# Grove_expansion_v4_for_box.net
KiCad netlist of a schematic drawn in EAGLE
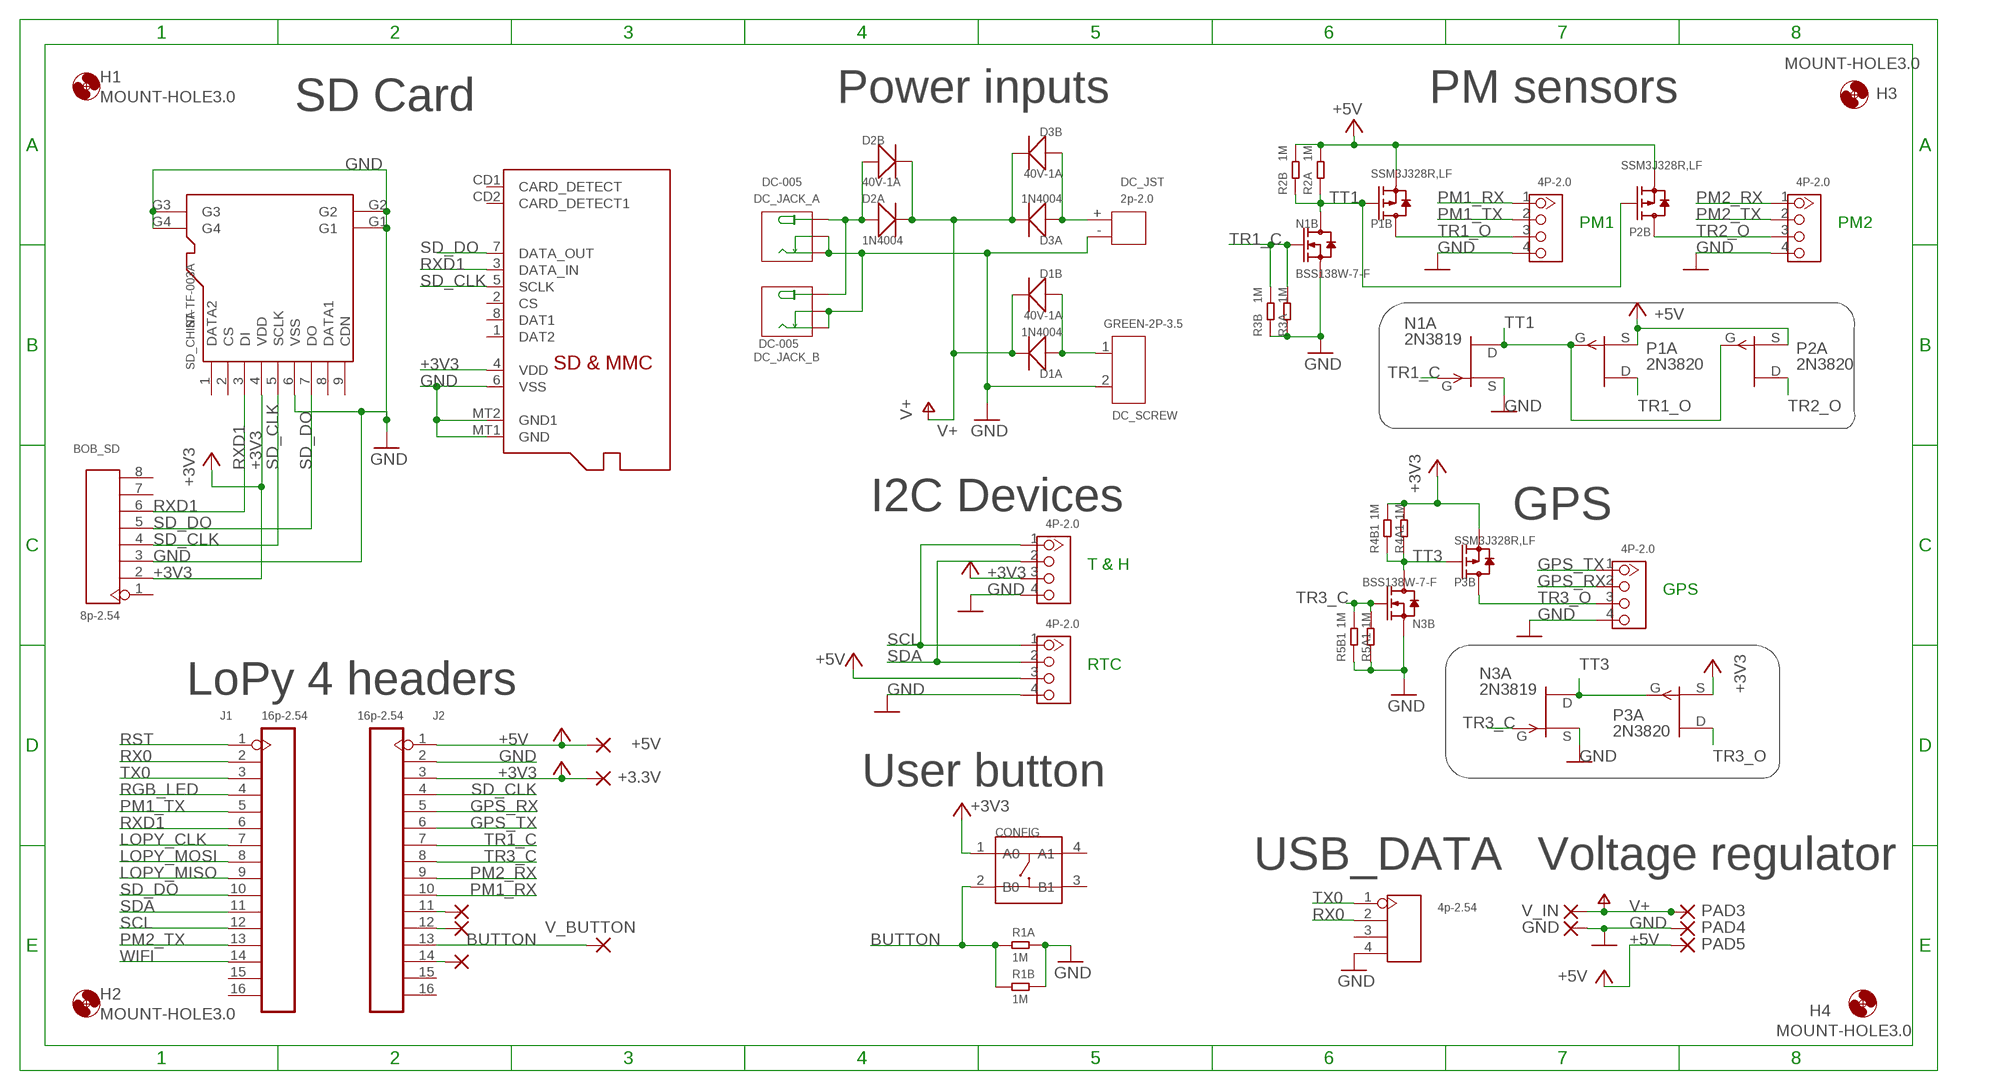
[diagram p0: schematic, sheet 1]

(export (version "E")
  (design (tool "Eeschema 10.0.6"))
  (components
    (comp (ref "+3.3V")
      (value "2,15/1,0")
      (footprint "eagle-import:2,15_1,0")
      (libsource (lib "eagle-import") (part "2,15/1,0"))
    )
    (comp (ref "+5V")
      (value "2,15/1,0")
      (footprint "eagle-import:2,15_1,0")
      (libsource (lib "eagle-import") (part "2,15/1,0"))
    )
    (comp (ref "BOB_SD")
      (value "8p-2.54")
      (footprint "eagle-import:H8-2.54")
      (fields (field (name "MPN") "F185-1108A1BSYC1"))
      (libsource (lib "eagle-import") (part "DIP-BLACK-FEMALE-HEADER-VERT(8P-2.54)"))
    )
    (comp (ref "CONFIG")
      (value "DIP-SWITCH-TACTILE-SPST-NO/TS-1109(4P-D6.0MM)'TS-1109'")
      (footprint "eagle-import:SW4-6.0X6.0X5.0MM")
      (libsource (lib "eagle-import") (part "DIP-SWITCH-TACTILE-SPST-NO/TS-1109(4P-D6.0MM)'TS-1109'"))
    )
    (comp (ref "D1A")
      (value "1N4004")
      (footprint "eagle-import:DO-41")
      (libsource (lib "eagle-import") (part "DIP-DIODE-400V-1A(DO-41)"))
    )
    (comp (ref "D1B")
      (value "40V-1A")
      (footprint "eagle-import:DO-214AC")
      (fields (field (name "MPN") "1N5819"))
      (libsource (lib "eagle-import") (part "SMD-DIODE-SCHOTTKY-40V-1A(DO-214AC)"))
    )
    (comp (ref "D2A")
      (value "1N4004")
      (footprint "eagle-import:DO-41")
      (libsource (lib "eagle-import") (part "DIP-DIODE-400V-1A(DO-41)"))
    )
    (comp (ref "D2B")
      (value "40V-1A")
      (footprint "eagle-import:DO-214AC")
      (fields (field (name "MPN") "1N5819"))
      (libsource (lib "eagle-import") (part "SMD-DIODE-SCHOTTKY-40V-1A(DO-214AC)"))
    )
    (comp (ref "D3A")
      (value "1N4004")
      (footprint "eagle-import:DO-41")
      (libsource (lib "eagle-import") (part "DIP-DIODE-400V-1A(DO-41)"))
    )
    (comp (ref "D3B")
      (value "40V-1A")
      (footprint "eagle-import:DO-214AC")
      (fields (field (name "MPN") "1N5819"))
      (libsource (lib "eagle-import") (part "SMD-DIODE-SCHOTTKY-40V-1A(DO-214AC)"))
    )
    (comp (ref "DC_JACK_A")
      (value "DC-005")
      (footprint "eagle-import:DCJ3P-14.2X11.0X9.0MM")
      (libsource (lib "eagle-import") (part "CONN-POWER-JACK-2.1MM(DC-005)"))
    )
    (comp (ref "DC_JACK_B")
      (value "DC-005")
      (footprint "eagle-import:DCJ3P-14.2X11.0X9.0MM")
      (libsource (lib "eagle-import") (part "CONN-POWER-JACK-2.1MM(DC-005)"))
    )
    (comp (ref "DC_JST")
      (value "2p-2.0")
      (footprint "eagle-import:H2-2.0-6X4.5MM")
      (libsource (lib "eagle-import") (part "DIP-JST-2P-2.0"))
    )
    (comp (ref "DC_SCREW")
      (value "GREEN-2P-3.5")
      (footprint "eagle-import:H2-3.5-7.0X7.0MM")
      (libsource (lib "eagle-import") (part "SCREW-TERMINAL-GREEN(2P-3.5)"))
    )
    (comp (ref "GND")
      (value "2,15/1,0")
      (footprint "eagle-import:2,15_1,0")
      (libsource (lib "eagle-import") (part "2,15/1,0"))
    )
    (comp (ref "GPS-(DIG)")
      (value "4P-2.0")
      (footprint "eagle-import:HW4-2.0")
      (libsource (lib "eagle-import") (part "GROVE-CONNECTOR-DIP(4P-2.0)"))
    )
    (comp (ref "H1")
      (value "MOUNT-HOLE3.0")
      (footprint "eagle-import:3,0")
      (libsource (lib "eagle-import") (part "MOUNT-HOLE3.0"))
    )
    (comp (ref "H2")
      (value "MOUNT-HOLE3.0")
      (footprint "eagle-import:3,0")
      (libsource (lib "eagle-import") (part "MOUNT-HOLE3.0"))
    )
    (comp (ref "H3")
      (value "MOUNT-HOLE3.0")
      (footprint "eagle-import:3,0")
      (libsource (lib "eagle-import") (part "MOUNT-HOLE3.0"))
    )
    (comp (ref "H4")
      (value "MOUNT-HOLE3.0")
      (footprint "eagle-import:3,0")
      (libsource (lib "eagle-import") (part "MOUNT-HOLE3.0"))
    )
    (comp (ref "J1")
      (value "16p-2.54")
      (footprint "eagle-import:H16-2.54")
      (fields (field (name "MPN") "P125-1116A0BS116AX"))
      (libsource (lib "eagle-import") (part "DIP-BLACK-MALE-HEADER-VERT(16P-2.54)"))
    )
    (comp (ref "J2")
      (value "16p-2.54")
      (footprint "eagle-import:H16-2.54")
      (fields (field (name "MPN") "P125-1116A0BS116AX"))
      (libsource (lib "eagle-import") (part "DIP-BLACK-MALE-HEADER-VERT(16P-2.54)"))
    )
    (comp (ref "N1A")
      (value "2N3819")
      (footprint "eagle-import:TO92")
      (libsource (lib "eagle-import") (part "2N3819"))
    )
    (comp (ref "N1B")
      (value "BSS138W-7-F")
      (footprint "eagle-import:SOT-23")
      (libsource (lib "eagle-import") (part "SMD-MOSFET-N-CH-50V-200MA-BSS138W-7-F(SOT-23)"))
    )
    (comp (ref "N3A")
      (value "2N3819")
      (footprint "eagle-import:TO92")
      (libsource (lib "eagle-import") (part "2N3819"))
    )
    (comp (ref "N3B")
      (value "BSS138W-7-F")
      (footprint "eagle-import:SOT-23")
      (libsource (lib "eagle-import") (part "SMD-MOSFET-N-CH-50V-200MA-BSS138W-7-F(SOT-23)"))
    )
    (comp (ref "P1A")
      (value "2N3820")
      (footprint "eagle-import:TO92")
      (libsource (lib "eagle-import") (part "2N3820"))
    )
    (comp (ref "P1B")
      (value "SSM3J328R,LF")
      (footprint "eagle-import:SOT-23")
      (libsource (lib "eagle-import") (part "SMD-MOSFET-P-CH-20V-6A-SSM3J328R(SOT-23)"))
    )
    (comp (ref "P2A")
      (value "2N3820")
      (footprint "eagle-import:TO92")
      (libsource (lib "eagle-import") (part "2N3820"))
    )
    (comp (ref "P2B")
      (value "SSM3J328R,LF")
      (footprint "eagle-import:SOT-23")
      (libsource (lib "eagle-import") (part "SMD-MOSFET-P-CH-20V-6A-SSM3J328R(SOT-23)"))
    )
    (comp (ref "P3A")
      (value "2N3820")
      (footprint "eagle-import:TO92")
      (libsource (lib "eagle-import") (part "2N3820"))
    )
    (comp (ref "P3B")
      (value "SSM3J328R,LF")
      (footprint "eagle-import:SOT-23")
      (libsource (lib "eagle-import") (part "SMD-MOSFET-P-CH-20V-6A-SSM3J328R(SOT-23)"))
    )
    (comp (ref "P13")
      (value "2,15/1,0")
      (footprint "eagle-import:2,15_1,0")
      (libsource (lib "eagle-import") (part "2,15/1,0"))
    )
    (comp (ref "P15")
      (value "2,15/1,0")
      (footprint "eagle-import:2,15_1,0")
      (libsource (lib "eagle-import") (part "2,15/1,0"))
    )
    (comp (ref "P16")
      (value "2,15/1,0")
      (footprint "eagle-import:2,15_1,0")
      (libsource (lib "eagle-import") (part "2,15/1,0"))
    )
    (comp (ref "PAD3")
      (value "1,6/0,8")
      (footprint "eagle-import:1,6_0,8")
      (libsource (lib "eagle-import") (part "1,6/0,8"))
    )
    (comp (ref "PAD4")
      (value "1,6/0,8")
      (footprint "eagle-import:1,6_0,8")
      (libsource (lib "eagle-import") (part "1,6/0,8"))
    )
    (comp (ref "PAD5")
      (value "1,6/0,8")
      (footprint "eagle-import:1,6_0,8")
      (libsource (lib "eagle-import") (part "1,6/0,8"))
    )
    (comp (ref "PM1-(UART)")
      (value "4P-2.0")
      (footprint "eagle-import:HW4-2.0")
      (libsource (lib "eagle-import") (part "GROVE-CONNECTOR-DIP(4P-2.0)"))
    )
    (comp (ref "PM2-(UART)")
      (value "4P-2.0")
      (footprint "eagle-import:HW4-2.0")
      (libsource (lib "eagle-import") (part "GROVE-CONNECTOR-DIP(4P-2.0)"))
    )
    (comp (ref "R1A")
      (value "1M")
      (footprint "eagle-import:PR-D2.3XL6.5MM")
      (fields (field (name "MPN") "FHCFR-1/4W-105J"))
      (libsource (lib "eagle-import") (part "DIP-RES-1M-5%-1/4W(PR-D2.3XL6.5MM)"))
    )
    (comp (ref "R1B")
      (value "1M")
      (footprint "eagle-import:R0603")
      (fields (field (name "MPN") "RC0603FR-071ML"))
      (libsource (lib "eagle-import") (part "SMD-RES-1M-1%-1/10W(0603)"))
    )
    (comp (ref "R2A")
      (value "1M")
      (footprint "eagle-import:PR-D2.3XL6.5MM")
      (fields (field (name "MPN") "FHCFR-1/4W-105J"))
      (libsource (lib "eagle-import") (part "DIP-RES-1M-5%-1/4W(PR-D2.3XL6.5MM)"))
    )
    (comp (ref "R2B")
      (value "1M")
      (footprint "eagle-import:R0603")
      (fields (field (name "MPN") "RC0603FR-071ML"))
      (libsource (lib "eagle-import") (part "SMD-RES-1M-1%-1/10W(0603)"))
    )
    (comp (ref "R3A")
      (value "1M")
      (footprint "eagle-import:PR-D2.3XL6.5MM")
      (fields (field (name "MPN") "FHCFR-1/4W-105J"))
      (libsource (lib "eagle-import") (part "DIP-RES-1M-5%-1/4W(PR-D2.3XL6.5MM)"))
    )
    (comp (ref "R3B")
      (value "1M")
      (footprint "eagle-import:R0603")
      (fields (field (name "MPN") "RC0603FR-071ML"))
      (libsource (lib "eagle-import") (part "SMD-RES-1M-1%-1/10W(0603)"))
    )
    (comp (ref "R4A1")
      (value "1M")
      (footprint "eagle-import:PR-D2.3XL6.5MM")
      (fields (field (name "MPN") "FHCFR-1/4W-105J"))
      (libsource (lib "eagle-import") (part "DIP-RES-1M-5%-1/4W(PR-D2.3XL6.5MM)"))
    )
    (comp (ref "R4B1")
      (value "1M")
      (footprint "eagle-import:R0603")
      (fields (field (name "MPN") "RC0603FR-071ML"))
      (libsource (lib "eagle-import") (part "SMD-RES-1M-1%-1/10W(0603)"))
    )
    (comp (ref "R5A1")
      (value "1M")
      (footprint "eagle-import:PR-D2.3XL6.5MM")
      (fields (field (name "MPN") "FHCFR-1/4W-105J"))
      (libsource (lib "eagle-import") (part "DIP-RES-1M-5%-1/4W(PR-D2.3XL6.5MM)"))
    )
    (comp (ref "R5B1")
      (value "1M")
      (footprint "eagle-import:R0603")
      (fields (field (name "MPN") "RC0603FR-071ML"))
      (libsource (lib "eagle-import") (part "SMD-RES-1M-1%-1/10W(0603)"))
    )
    (comp (ref "RTC-(I2C)")
      (value "4P-2.0")
      (footprint "eagle-import:HW4-2.0")
      (libsource (lib "eagle-import") (part "GROVE-CONNECTOR-DIP(4P-2.0)"))
    )
    (comp (ref "SD_CHINA")
      (value "ST-TF-003A")
      (footprint "eagle-import:MICRO-SD9+4P-SMD-16.1X14.5X1.85MM")
      (libsource (lib "eagle-import") (part "MICRO-SD-CARD-SOCKET-9P(ST-TF-003A)"))
    )
    (comp (ref "SD_UK")
      (value "MICROSD")
      (footprint "eagle-import:MICROSD")
      (libsource (lib "eagle-import") (part "MICROSD"))
    )
    (comp (ref "TH-(I2C)")
      (value "4P-2.0")
      (footprint "eagle-import:HW4-2.0")
      (libsource (lib "eagle-import") (part "GROVE-CONNECTOR-DIP(4P-2.0)"))
    )
    (comp (ref "USB_DATA")
      (value "4p-2.54")
      (footprint "eagle-import:H4-2.54")
      (fields (field (name "MPN") "F185-1104A1BSYA1"))
      (libsource (lib "eagle-import") (part "DIP-BLACK-FEMALE-HEADER-VERT(4P-2.54)"))
    )
    (comp (ref "V_BUTTON")
      (value "2,15/1,0")
      (footprint "eagle-import:2,15_1,0")
      (libsource (lib "eagle-import") (part "2,15/1,0"))
    )
    (comp (ref "V_IN")
      (value "2,15/1,0")
      (footprint "eagle-import:2,15_1,0")
      (libsource (lib "eagle-import") (part "2,15/1,0"))
    )
  )
  (nets
    (net (code "1") (name "+3V3") (class "Default")
      (node (ref "+3.3V") (pin "1") (pinfunction "P_1") (pintype "passive"))
      (node (ref "BOB_SD") (pin "2") (pinfunction "2_2") (pintype "bidirectional"))
      (node (ref "CONFIG") (pin "1") (pinfunction "A0_1") (pintype "bidirectional"))
      (node (ref "J2") (pin "3") (pinfunction "3_3") (pintype "passive"))
      (node (ref "P3A") (pin "1") (pinfunction "S_1") (pintype "passive"))
      (node (ref "P3B") (pin "2") (pinfunction "S_2") (pintype "passive"))
      (node (ref "R4A1") (pin "2") (pinfunction "2_2") (pintype "passive"))
      (node (ref "R4B1") (pin "2") (pinfunction "2_2") (pintype "passive"))
      (node (ref "SD_CHINA") (pin "4") (pinfunction "VDD_4") (pintype "bidirectional"))
      (node (ref "SD_UK") (pin "4") (pinfunction "VDD_4") (pintype "power_in"))
      (node (ref "TH-(I2C)") (pin "3") (pinfunction "3_3") (pintype "bidirectional"))
    )
    (net (code "2") (name "+5V") (class "Default")
      (node (ref "+5V") (pin "1") (pinfunction "P_1") (pintype "passive"))
      (node (ref "J2") (pin "1") (pinfunction "1_1") (pintype "passive"))
      (node (ref "P1A") (pin "1") (pinfunction "S_1") (pintype "passive"))
      (node (ref "P1B") (pin "2") (pinfunction "S_2") (pintype "passive"))
      (node (ref "P2A") (pin "1") (pinfunction "S_1") (pintype "passive"))
      (node (ref "P2B") (pin "2") (pinfunction "S_2") (pintype "passive"))
      (node (ref "PAD5") (pin "1") (pinfunction "P_1") (pintype "passive"))
      (node (ref "R2A") (pin "2") (pinfunction "2_2") (pintype "passive"))
      (node (ref "R2B") (pin "2") (pinfunction "2_2") (pintype "passive"))
      (node (ref "RTC-(I2C)") (pin "3") (pinfunction "3_3") (pintype "bidirectional"))
    )
    (net (code "3") (name "BUTTON") (class "Default")
      (node (ref "CONFIG") (pin "2") (pinfunction "B0_2") (pintype "bidirectional"))
      (node (ref "J2") (pin "13") (pinfunction "13_13") (pintype "passive"))
      (node (ref "R1A") (pin "1") (pinfunction "1_1") (pintype "passive"))
      (node (ref "R1B") (pin "1") (pinfunction "1_1") (pintype "passive"))
      (node (ref "V_BUTTON") (pin "1") (pinfunction "P_1") (pintype "passive"))
    )
    (net (code "4") (name "GND") (class "Default")
      (node (ref "BOB_SD") (pin "3") (pinfunction "3_3") (pintype "bidirectional"))
      (node (ref "DC_JACK_A") (pin "-1") (pinfunction "-_-1") (pintype "bidirectional"))
      (node (ref "DC_JACK_A") (pin "-2") (pinfunction "CDN_-2") (pintype "bidirectional"))
      (node (ref "DC_JACK_B") (pin "-1") (pinfunction "-_-1") (pintype "bidirectional"))
      (node (ref "DC_JACK_B") (pin "-2") (pinfunction "CDN_-2") (pintype "bidirectional"))
      (node (ref "DC_JST") (pin "-") (pinfunction "P$2_-") (pintype "bidirectional"))
      (node (ref "DC_SCREW") (pin "2") (pinfunction "2_2") (pintype "bidirectional"))
      (node (ref "GND") (pin "1") (pinfunction "P_1") (pintype "passive"))
      (node (ref "GPS-(DIG)") (pin "4") (pinfunction "4_4") (pintype "bidirectional"))
      (node (ref "J2") (pin "2") (pinfunction "2_2") (pintype "passive"))
      (node (ref "N1A") (pin "3") (pinfunction "S_3") (pintype "passive"))
      (node (ref "N1B") (pin "2") (pinfunction "S_2") (pintype "passive"))
      (node (ref "N3A") (pin "3") (pinfunction "S_3") (pintype "passive"))
      (node (ref "N3B") (pin "2") (pinfunction "S_2") (pintype "passive"))
      (node (ref "PAD4") (pin "1") (pinfunction "P_1") (pintype "passive"))
      (node (ref "PM1-(UART)") (pin "4") (pinfunction "4_4") (pintype "bidirectional"))
      (node (ref "PM2-(UART)") (pin "4") (pinfunction "4_4") (pintype "bidirectional"))
      (node (ref "R1A") (pin "2") (pinfunction "2_2") (pintype "passive"))
      (node (ref "R1B") (pin "2") (pinfunction "2_2") (pintype "passive"))
      (node (ref "R3A") (pin "1") (pinfunction "1_1") (pintype "passive"))
      (node (ref "R3B") (pin "1") (pinfunction "1_1") (pintype "passive"))
      (node (ref "R5A1") (pin "1") (pinfunction "1_1") (pintype "passive"))
      (node (ref "R5B1") (pin "1") (pinfunction "1_1") (pintype "passive"))
      (node (ref "RTC-(I2C)") (pin "4") (pinfunction "4_4") (pintype "bidirectional"))
      (node (ref "SD_CHINA") (pin "6") (pinfunction "VSS_6") (pintype "bidirectional"))
      (node (ref "SD_CHINA") (pin "G1") (pinfunction "G1_G1") (pintype "bidirectional"))
      (node (ref "SD_CHINA") (pin "G2") (pinfunction "G2_G2") (pintype "bidirectional"))
      (node (ref "SD_CHINA") (pin "G3") (pinfunction "G3_G3") (pintype "bidirectional"))
      (node (ref "SD_CHINA") (pin "G4") (pinfunction "G4_G4") (pintype "bidirectional"))
      (node (ref "SD_UK") (pin "6") (pinfunction "VSS_6") (pintype "power_in"))
      (node (ref "SD_UK") (pin "MT1") (pinfunction "GND_MT1") (pintype "power_in"))
      (node (ref "SD_UK") (pin "MT2") (pinfunction "GND1_MT2") (pintype "power_in"))
      (node (ref "TH-(I2C)") (pin "4") (pinfunction "4_4") (pintype "bidirectional"))
      (node (ref "USB_DATA") (pin "4") (pinfunction "P$4_4") (pintype "bidirectional"))
    )
    (net (code "5") (name "GPS_RX") (class "Default")
      (node (ref "GPS-(DIG)") (pin "2") (pinfunction "2_2") (pintype "bidirectional"))
      (node (ref "J2") (pin "5") (pinfunction "5_5") (pintype "passive"))
    )
    (net (code "6") (name "GPS_TX") (class "Default")
      (node (ref "GPS-(DIG)") (pin "1") (pinfunction "1_1") (pintype "bidirectional"))
      (node (ref "J2") (pin "6") (pinfunction "6_6") (pintype "passive"))
    )
    (net (code "7") (name "LOPY_CLK") (class "Default")
      (node (ref "J1") (pin "7") (pinfunction "7_7") (pintype "passive"))
    )
    (net (code "8") (name "LOPY_MISO") (class "Default")
      (node (ref "J1") (pin "9") (pinfunction "9_9") (pintype "passive"))
    )
    (net (code "9") (name "LOPY_MOSI") (class "Default")
      (node (ref "J1") (pin "8") (pinfunction "8_8") (pintype "passive"))
    )
    (net (code "10") (name "Net-(D1A-+)") (class "Default")
      (node (ref "D1A") (pin "1") (pinfunction "+_1") (pintype "passive"))
      (node (ref "D1B") (pin "1") (pinfunction "+_1") (pintype "passive"))
      (node (ref "DC_SCREW") (pin "1") (pinfunction "1_1") (pintype "bidirectional"))
    )
    (net (code "11") (name "Net-(D2A-+)") (class "Default")
      (node (ref "D2A") (pin "1") (pinfunction "+_1") (pintype "passive"))
      (node (ref "D2B") (pin "1") (pinfunction "+_1") (pintype "passive"))
      (node (ref "DC_JACK_A") (pin "+") (pinfunction "+_+") (pintype "bidirectional"))
      (node (ref "DC_JACK_B") (pin "+") (pinfunction "+_+") (pintype "bidirectional"))
    )
    (net (code "12") (name "Net-(D3A-+)") (class "Default")
      (node (ref "D3A") (pin "1") (pinfunction "+_1") (pintype "passive"))
      (node (ref "D3B") (pin "1") (pinfunction "+_1") (pintype "passive"))
      (node (ref "DC_JST") (pin "+") (pinfunction "P$1_+") (pintype "bidirectional"))
    )
    (net (code "13") (name "Net-(P13-P)") (class "Default")
      (node (ref "J2") (pin "14") (pinfunction "14_14") (pintype "passive"))
      (node (ref "P13") (pin "1") (pinfunction "P_1") (pintype "passive"))
    )
    (net (code "14") (name "Net-(P15-P)") (class "Default")
      (node (ref "J2") (pin "12") (pinfunction "12_12") (pintype "passive"))
      (node (ref "P15") (pin "1") (pinfunction "P_1") (pintype "passive"))
    )
    (net (code "15") (name "Net-(P16-P)") (class "Default")
      (node (ref "J2") (pin "11") (pinfunction "11_11") (pintype "passive"))
      (node (ref "P16") (pin "1") (pinfunction "P_1") (pintype "passive"))
    )
    (net (code "16") (name "PM1_RX") (class "Default")
      (node (ref "J2") (pin "10") (pinfunction "10_10") (pintype "passive"))
      (node (ref "PM1-(UART)") (pin "1") (pinfunction "1_1") (pintype "bidirectional"))
    )
    (net (code "17") (name "PM1_TX") (class "Default")
      (node (ref "J1") (pin "5") (pinfunction "5_5") (pintype "passive"))
      (node (ref "PM1-(UART)") (pin "2") (pinfunction "2_2") (pintype "bidirectional"))
    )
    (net (code "18") (name "PM2_RX") (class "Default")
      (node (ref "J2") (pin "9") (pinfunction "9_9") (pintype "passive"))
      (node (ref "PM2-(UART)") (pin "1") (pinfunction "1_1") (pintype "bidirectional"))
    )
    (net (code "19") (name "PM2_TX") (class "Default")
      (node (ref "J1") (pin "13") (pinfunction "13_13") (pintype "passive"))
      (node (ref "PM2-(UART)") (pin "2") (pinfunction "2_2") (pintype "bidirectional"))
    )
    (net (code "20") (name "RGB_LED") (class "Default")
      (node (ref "J1") (pin "4") (pinfunction "4_4") (pintype "passive"))
    )
    (net (code "21") (name "RST") (class "Default")
      (node (ref "J1") (pin "1") (pinfunction "1_1") (pintype "passive"))
    )
    (net (code "22") (name "RX0") (class "Default")
      (node (ref "J1") (pin "2") (pinfunction "2_2") (pintype "passive"))
      (node (ref "USB_DATA") (pin "2") (pinfunction "P$2_2") (pintype "bidirectional"))
    )
    (net (code "23") (name "RXD1") (class "Default")
      (node (ref "BOB_SD") (pin "6") (pinfunction "6_6") (pintype "bidirectional"))
      (node (ref "J1") (pin "6") (pinfunction "6_6") (pintype "passive"))
      (node (ref "SD_CHINA") (pin "3") (pinfunction "DI_3") (pintype "bidirectional"))
      (node (ref "SD_UK") (pin "3") (pinfunction "DATA_IN_3") (pintype "input"))
    )
    (net (code "24") (name "SCL") (class "Default")
      (node (ref "J1") (pin "12") (pinfunction "12_12") (pintype "passive"))
      (node (ref "RTC-(I2C)") (pin "1") (pinfunction "1_1") (pintype "bidirectional"))
      (node (ref "TH-(I2C)") (pin "1") (pinfunction "1_1") (pintype "bidirectional"))
    )
    (net (code "25") (name "SDA") (class "Default")
      (node (ref "J1") (pin "11") (pinfunction "11_11") (pintype "passive"))
      (node (ref "RTC-(I2C)") (pin "2") (pinfunction "2_2") (pintype "bidirectional"))
      (node (ref "TH-(I2C)") (pin "2") (pinfunction "2_2") (pintype "bidirectional"))
    )
    (net (code "26") (name "SD_CLK") (class "Default")
      (node (ref "BOB_SD") (pin "4") (pinfunction "4_4") (pintype "bidirectional"))
      (node (ref "J2") (pin "4") (pinfunction "4_4") (pintype "passive"))
      (node (ref "SD_CHINA") (pin "5") (pinfunction "SCLK_5") (pintype "bidirectional"))
      (node (ref "SD_UK") (pin "5") (pinfunction "SCLK_5") (pintype "input"))
    )
    (net (code "27") (name "SD_DO") (class "Default")
      (node (ref "BOB_SD") (pin "5") (pinfunction "5_5") (pintype "bidirectional"))
      (node (ref "J1") (pin "10") (pinfunction "10_10") (pintype "passive"))
      (node (ref "SD_CHINA") (pin "7") (pinfunction "DO_7") (pintype "bidirectional"))
      (node (ref "SD_UK") (pin "7") (pinfunction "DATA_OUT_7") (pintype "output"))
    )
    (net (code "28") (name "TR1_C") (class "Default")
      (node (ref "J2") (pin "7") (pinfunction "7_7") (pintype "passive"))
      (node (ref "N1A") (pin "2") (pinfunction "G_2") (pintype "passive"))
      (node (ref "N1B") (pin "1") (pinfunction "G_1") (pintype "passive"))
      (node (ref "R3A") (pin "2") (pinfunction "2_2") (pintype "passive"))
      (node (ref "R3B") (pin "2") (pinfunction "2_2") (pintype "passive"))
    )
    (net (code "29") (name "TR1_O") (class "Default")
      (node (ref "P1A") (pin "3") (pinfunction "D_3") (pintype "passive"))
      (node (ref "P1B") (pin "3") (pinfunction "D_3") (pintype "passive"))
      (node (ref "PM1-(UART)") (pin "3") (pinfunction "3_3") (pintype "bidirectional"))
    )
    (net (code "30") (name "TR2_O") (class "Default")
      (node (ref "P2A") (pin "3") (pinfunction "D_3") (pintype "passive"))
      (node (ref "P2B") (pin "3") (pinfunction "D_3") (pintype "passive"))
      (node (ref "PM2-(UART)") (pin "3") (pinfunction "3_3") (pintype "bidirectional"))
    )
    (net (code "31") (name "TR3_C") (class "Default")
      (node (ref "J2") (pin "8") (pinfunction "8_8") (pintype "passive"))
      (node (ref "N3A") (pin "2") (pinfunction "G_2") (pintype "passive"))
      (node (ref "N3B") (pin "1") (pinfunction "G_1") (pintype "passive"))
      (node (ref "R5A1") (pin "2") (pinfunction "2_2") (pintype "passive"))
      (node (ref "R5B1") (pin "2") (pinfunction "2_2") (pintype "passive"))
    )
    (net (code "32") (name "TR3_O") (class "Default")
      (node (ref "GPS-(DIG)") (pin "3") (pinfunction "3_3") (pintype "bidirectional"))
      (node (ref "P3A") (pin "3") (pinfunction "D_3") (pintype "passive"))
      (node (ref "P3B") (pin "3") (pinfunction "D_3") (pintype "passive"))
    )
    (net (code "33") (name "TT1") (class "Default")
      (node (ref "N1A") (pin "1") (pinfunction "D_1") (pintype "passive"))
      (node (ref "N1B") (pin "3") (pinfunction "D_3") (pintype "passive"))
      (node (ref "P1A") (pin "2") (pinfunction "G_2") (pintype "passive"))
      (node (ref "P1B") (pin "1") (pinfunction "G_1") (pintype "passive"))
      (node (ref "P2A") (pin "2") (pinfunction "G_2") (pintype "passive"))
      (node (ref "P2B") (pin "1") (pinfunction "G_1") (pintype "passive"))
      (node (ref "R2A") (pin "1") (pinfunction "1_1") (pintype "passive"))
      (node (ref "R2B") (pin "1") (pinfunction "1_1") (pintype "passive"))
    )
    (net (code "34") (name "TT3") (class "Default")
      (node (ref "N3A") (pin "1") (pinfunction "D_1") (pintype "passive"))
      (node (ref "N3B") (pin "3") (pinfunction "D_3") (pintype "passive"))
      (node (ref "P3A") (pin "2") (pinfunction "G_2") (pintype "passive"))
      (node (ref "P3B") (pin "1") (pinfunction "G_1") (pintype "passive"))
      (node (ref "R4A1") (pin "1") (pinfunction "1_1") (pintype "passive"))
      (node (ref "R4B1") (pin "1") (pinfunction "1_1") (pintype "passive"))
    )
    (net (code "35") (name "TX0") (class "Default")
      (node (ref "J1") (pin "3") (pinfunction "3_3") (pintype "passive"))
      (node (ref "USB_DATA") (pin "1") (pinfunction "P$1_1") (pintype "bidirectional"))
    )
    (net (code "36") (name "V+") (class "Default")
      (node (ref "D1A") (pin "2") (pinfunction "-_2") (pintype "passive"))
      (node (ref "D1B") (pin "2") (pinfunction "-_2") (pintype "passive"))
      (node (ref "D2A") (pin "2") (pinfunction "-_2") (pintype "passive"))
      (node (ref "D2B") (pin "2") (pinfunction "-_2") (pintype "passive"))
      (node (ref "D3A") (pin "2") (pinfunction "-_2") (pintype "passive"))
      (node (ref "D3B") (pin "2") (pinfunction "-_2") (pintype "passive"))
      (node (ref "PAD3") (pin "1") (pinfunction "P_1") (pintype "passive"))
      (node (ref "V_IN") (pin "1") (pinfunction "P_1") (pintype "passive"))
    )
    (net (code "37") (name "WIFI") (class "Default")
      (node (ref "J1") (pin "14") (pinfunction "14_14") (pintype "passive"))
    )
    (net (code "38") (name "unconnected-(BOB_SD-Pad1)") (class "Default")
      (node (ref "BOB_SD") (pin "1") (pinfunction "1_1") (pintype "bidirectional"))
    )
    (net (code "39") (name "unconnected-(BOB_SD-Pad7)") (class "Default")
      (node (ref "BOB_SD") (pin "7") (pinfunction "7_7") (pintype "bidirectional"))
    )
    (net (code "40") (name "unconnected-(BOB_SD-Pad8)") (class "Default")
      (node (ref "BOB_SD") (pin "8") (pinfunction "8_8") (pintype "bidirectional"))
    )
    (net (code "41") (name "unconnected-(CONFIG-A1-Pad4)") (class "Default")
      (node (ref "CONFIG") (pin "4") (pinfunction "A1_4") (pintype "bidirectional"))
    )
    (net (code "42") (name "unconnected-(CONFIG-B1-Pad3)") (class "Default")
      (node (ref "CONFIG") (pin "3") (pinfunction "B1_3") (pintype "bidirectional"))
    )
    (net (code "43") (name "unconnected-(J1-Pad15)") (class "Default")
      (node (ref "J1") (pin "15") (pinfunction "15_15") (pintype "passive"))
    )
    (net (code "44") (name "unconnected-(J1-Pad16)") (class "Default")
      (node (ref "J1") (pin "16") (pinfunction "16_16") (pintype "passive"))
    )
    (net (code "45") (name "unconnected-(J2-Pad15)") (class "Default")
      (node (ref "J2") (pin "15") (pinfunction "15_15") (pintype "passive"))
    )
    (net (code "46") (name "unconnected-(J2-Pad16)") (class "Default")
      (node (ref "J2") (pin "16") (pinfunction "16_16") (pintype "passive"))
    )
    (net (code "47") (name "unconnected-(SD_CHINA-CDN-Pad9)") (class "Default")
      (node (ref "SD_CHINA") (pin "9") (pinfunction "CDN_9") (pintype "bidirectional"))
    )
    (net (code "48") (name "unconnected-(SD_CHINA-CS-Pad2)") (class "Default")
      (node (ref "SD_CHINA") (pin "2") (pinfunction "CS_2") (pintype "bidirectional"))
    )
    (net (code "49") (name "unconnected-(SD_CHINA-DATA1-Pad8)") (class "Default")
      (node (ref "SD_CHINA") (pin "8") (pinfunction "DATA1_8") (pintype "bidirectional"))
    )
    (net (code "50") (name "unconnected-(SD_CHINA-DATA2-Pad1)") (class "Default")
      (node (ref "SD_CHINA") (pin "1") (pinfunction "DATA2_1") (pintype "bidirectional"))
    )
    (net (code "51") (name "unconnected-(SD_UK-CARD_DETECT-PadCD1)") (class "Default")
      (node (ref "SD_UK") (pin "CD1") (pinfunction "CARD_DETECT_CD1") (pintype "passive"))
    )
    (net (code "52") (name "unconnected-(SD_UK-CARD_DETECT1-PadCD2)") (class "Default")
      (node (ref "SD_UK") (pin "CD2") (pinfunction "CARD_DETECT1_CD2") (pintype "passive"))
    )
    (net (code "53") (name "unconnected-(SD_UK-CS-Pad2)") (class "Default")
      (node (ref "SD_UK") (pin "2") (pinfunction "CS_2") (pintype "input"))
    )
    (net (code "54") (name "unconnected-(SD_UK-DAT1-Pad8)") (class "Default")
      (node (ref "SD_UK") (pin "8") (pinfunction "DAT1_8") (pintype "bidirectional"))
    )
    (net (code "55") (name "unconnected-(SD_UK-DAT2-Pad1)") (class "Default")
      (node (ref "SD_UK") (pin "1") (pinfunction "DAT2_1") (pintype "bidirectional"))
    )
    (net (code "56") (name "unconnected-(USB_DATA-P$3-Pad3)") (class "Default")
      (node (ref "USB_DATA") (pin "3") (pinfunction "P$3_3") (pintype "bidirectional"))
    )
  )
)
